# usbhub.net
KiCad netlist of a schematic drawn in Altium Designer
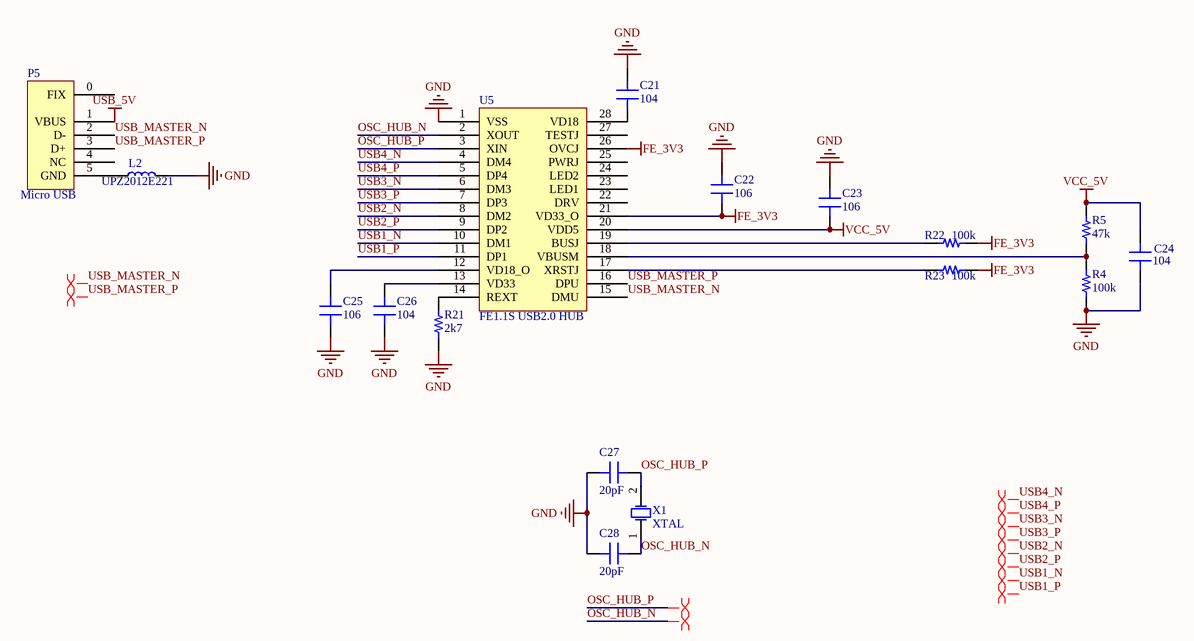
[diagram p0: usbhub.SchDoc]

(export (version "E")
  (design (tool "Eeschema 10.0.6"))
  (components
    (comp (ref "C21")
      (value "104")
      (footprint "C0603/1608")
      (description "陶瓷电容")
      (libsource (lib "Devices") (part "陶瓷电容"))
    )
    (comp (ref "C22")
      (value "106")
      (footprint "C0603/1608")
      (description "陶瓷电容")
      (libsource (lib "Devices") (part "陶瓷电容"))
    )
    (comp (ref "C23")
      (value "106")
      (footprint "C0603/1608")
      (description "陶瓷电容")
      (libsource (lib "Devices") (part "陶瓷电容"))
    )
    (comp (ref "C24")
      (value "104")
      (footprint "C0603/1608")
      (description "陶瓷电容")
      (libsource (lib "Devices") (part "陶瓷电容"))
    )
    (comp (ref "C25")
      (value "106")
      (footprint "C0603/1608")
      (description "陶瓷电容")
      (libsource (lib "Devices") (part "陶瓷电容"))
    )
    (comp (ref "C26")
      (value "104")
      (footprint "C0603/1608")
      (description "陶瓷电容")
      (libsource (lib "Devices") (part "陶瓷电容"))
    )
    (comp (ref "C27")
      (value "20pF")
      (footprint "C0603/1608")
      (description "陶瓷电容")
      (libsource (lib "Devices") (part "陶瓷电容"))
    )
    (comp (ref "C28")
      (value "20pF")
      (footprint "C0603/1608")
      (description "陶瓷电容")
      (libsource (lib "Devices") (part "陶瓷电容"))
    )
    (comp (ref "L2")
      (value "UPZ2012E221")
      (footprint "L0805/2012")
      (description "贴片磁珠")
      (libsource (lib "WMJ2019_Devices") (part "磁珠"))
    )
    (comp (ref "P5")
      (value "Micro USB")
      (footprint "Micro USB")
      (description "Micro USB底座")
      (libsource (lib "Devices") (part "Micro USB"))
    )
    (comp (ref "R4")
      (value "100k")
      (footprint "R0603/1608")
      (description "电阻")
      (libsource (lib "Devices") (part "电阻"))
    )
    (comp (ref "R5")
      (value "47k")
      (footprint "R0603/1608")
      (description "电阻")
      (libsource (lib "Devices") (part "电阻"))
    )
    (comp (ref "R21")
      (value "2k7")
      (footprint "R0603/1608")
      (description "电阻")
      (libsource (lib "Devices") (part "电阻"))
    )
    (comp (ref "R22")
      (value "100k")
      (footprint "R0603/1608")
      (description "电阻")
      (libsource (lib "Devices") (part "电阻"))
    )
    (comp (ref "R23")
      (value "100k")
      (footprint "R0603/1608")
      (description "电阻")
      (libsource (lib "Devices") (part "电阻"))
    )
    (comp (ref "U5")
      (value "FE1.1S USB2.0 HUB")
      (footprint "SOP65P780-28M")
      (libsource (lib "Devices") (part "FE1.1S USB2.0 HUB"))
    )
    (comp (ref "X1")
      (value "XTAL")
      (footprint "XTAL-49S")
      (description "晶振")
      (fields (field (name "PUBLISHER") "Altium Limited"))
      (libsource (lib "Devices") (part "晶振"))
    )
  )
  (nets
    (net (code "1") (name "/OSC_HUB_N") (class "Default")
      (node (ref "C28") (pin "1") (pintype "passive"))
      (node (ref "U5") (pin "2") (pinfunction "XOUT_2") (pintype "passive"))
      (node (ref "X1") (pin "1") (pinfunction "OSC1_1") (pintype "passive"))
    )
    (net (code "2") (name "/OSC_HUB_P") (class "Default")
      (node (ref "C27") (pin "1") (pintype "passive"))
      (node (ref "U5") (pin "3") (pinfunction "XIN_3") (pintype "passive"))
      (node (ref "X1") (pin "2") (pinfunction "OSC2_2") (pintype "passive"))
    )
    (net (code "3") (name "/USB1_N") (class "Default")
      (node (ref "U5") (pin "10") (pinfunction "DM1_10") (pintype "passive"))
    )
    (net (code "4") (name "/USB1_P") (class "Default")
      (node (ref "U5") (pin "11") (pinfunction "DP1_11") (pintype "passive"))
    )
    (net (code "5") (name "/USB2_N") (class "Default")
      (node (ref "U5") (pin "8") (pinfunction "DM2_8") (pintype "passive"))
    )
    (net (code "6") (name "/USB2_P") (class "Default")
      (node (ref "U5") (pin "9") (pinfunction "DP2_9") (pintype "passive"))
    )
    (net (code "7") (name "/USB3_N") (class "Default")
      (node (ref "U5") (pin "6") (pinfunction "DM3_6") (pintype "passive"))
    )
    (net (code "8") (name "/USB3_P") (class "Default")
      (node (ref "U5") (pin "7") (pinfunction "DP3_7") (pintype "passive"))
    )
    (net (code "9") (name "/USB4_N") (class "Default")
      (node (ref "U5") (pin "4") (pinfunction "DM4_4") (pintype "passive"))
    )
    (net (code "10") (name "/USB4_P") (class "Default")
      (node (ref "U5") (pin "5") (pinfunction "DP4_5") (pintype "passive"))
    )
    (net (code "11") (name "/USB_MASTER_N") (class "Default")
      (node (ref "P5") (pin "2") (pinfunction "D-_2") (pintype "passive"))
      (node (ref "U5") (pin "15") (pinfunction "DMU_15") (pintype "passive"))
    )
    (net (code "12") (name "/USB_MASTER_P") (class "Default")
      (node (ref "P5") (pin "3") (pinfunction "D+_3") (pintype "passive"))
      (node (ref "U5") (pin "16") (pinfunction "DPU_16") (pintype "passive"))
    )
    (net (code "13") (name "FE_3V3") (class "Default")
      (node (ref "C22") (pin "2") (pintype "passive"))
      (node (ref "R22") (pin "1") (pintype "passive"))
      (node (ref "R23") (pin "1") (pintype "passive"))
      (node (ref "U5") (pin "21") (pinfunction "VD33_O_21") (pintype "passive"))
      (node (ref "U5") (pin "26") (pinfunction "OVCJ_26") (pintype "passive"))
    )
    (net (code "14") (name "GND") (class "Default")
      (node (ref "C21") (pin "1") (pintype "passive"))
      (node (ref "C22") (pin "1") (pintype "passive"))
      (node (ref "C23") (pin "1") (pintype "passive"))
      (node (ref "C24") (pin "2") (pintype "passive"))
      (node (ref "C25") (pin "2") (pintype "passive"))
      (node (ref "C26") (pin "2") (pintype "passive"))
      (node (ref "C27") (pin "2") (pintype "passive"))
      (node (ref "C28") (pin "2") (pintype "passive"))
      (node (ref "L2") (pin "1") (pinfunction "1_1") (pintype "passive"))
      (node (ref "R21") (pin "1") (pintype "passive"))
      (node (ref "R4") (pin "2") (pintype "passive"))
      (node (ref "U5") (pin "1") (pinfunction "VSS_1") (pintype "passive"))
    )
    (net (code "15") (name "Net-(P5-GND)") (class "Default")
      (node (ref "L2") (pin "2") (pinfunction "2_2") (pintype "passive"))
      (node (ref "P5") (pin "5") (pinfunction "GND_5") (pintype "passive"))
    )
    (net (code "16") (name "Net-(U5-BUSJ)") (class "Default")
      (node (ref "R22") (pin "2") (pintype "passive"))
      (node (ref "U5") (pin "19") (pinfunction "BUSJ_19") (pintype "passive"))
    )
    (net (code "17") (name "Net-(U5-REXT)") (class "Default")
      (node (ref "R21") (pin "2") (pintype "passive"))
      (node (ref "U5") (pin "14") (pinfunction "REXT_14") (pintype "passive"))
    )
    (net (code "18") (name "Net-(U5-VBUSM)") (class "Default")
      (node (ref "R4") (pin "1") (pintype "passive"))
      (node (ref "R5") (pin "2") (pintype "passive"))
      (node (ref "U5") (pin "18") (pinfunction "VBUSM_18") (pintype "passive"))
    )
    (net (code "19") (name "Net-(U5-VD18)") (class "Default")
      (node (ref "C21") (pin "2") (pintype "passive"))
      (node (ref "U5") (pin "28") (pinfunction "VD18_28") (pintype "passive"))
    )
    (net (code "20") (name "Net-(U5-VD18_O)") (class "Default")
      (node (ref "C25") (pin "1") (pintype "passive"))
      (node (ref "U5") (pin "12") (pinfunction "VD18_O_12") (pintype "passive"))
    )
    (net (code "21") (name "Net-(U5-VD33)") (class "Default")
      (node (ref "C26") (pin "1") (pintype "passive"))
      (node (ref "U5") (pin "13") (pinfunction "VD33_13") (pintype "passive"))
    )
    (net (code "22") (name "Net-(U5-XRSTJ)") (class "Default")
      (node (ref "R23") (pin "2") (pintype "passive"))
      (node (ref "U5") (pin "17") (pinfunction "XRSTJ_17") (pintype "passive"))
    )
    (net (code "23") (name "USB_5V") (class "Default")
      (node (ref "P5") (pin "1") (pinfunction "VBUS_1") (pintype "passive"))
    )
    (net (code "24") (name "VCC_5V") (class "Default")
      (node (ref "C23") (pin "2") (pintype "passive"))
      (node (ref "C24") (pin "1") (pintype "passive"))
      (node (ref "R5") (pin "1") (pintype "passive"))
      (node (ref "U5") (pin "20") (pinfunction "VDD5_20") (pintype "passive"))
    )
    (net (code "25") (name "unconnected-(P5-FIX-Pad0)") (class "Default")
      (node (ref "P5") (pin "0") (pinfunction "FIX_0") (pintype "passive"))
    )
    (net (code "26") (name "unconnected-(P5-NC-Pad4)") (class "Default")
      (node (ref "P5") (pin "4") (pinfunction "NC_4") (pintype "passive"))
    )
    (net (code "27") (name "unconnected-(U5-DRV-Pad22)") (class "Default")
      (node (ref "U5") (pin "22") (pinfunction "DRV_22") (pintype "passive"))
    )
    (net (code "28") (name "unconnected-(U5-LED1-Pad23)") (class "Default")
      (node (ref "U5") (pin "23") (pinfunction "LED1_23") (pintype "passive"))
    )
    (net (code "29") (name "unconnected-(U5-LED2-Pad24)") (class "Default")
      (node (ref "U5") (pin "24") (pinfunction "LED2_24") (pintype "passive"))
    )
    (net (code "30") (name "unconnected-(U5-PWRJ-Pad25)") (class "Default")
      (node (ref "U5") (pin "25") (pinfunction "PWRJ_25") (pintype "passive"))
    )
    (net (code "31") (name "unconnected-(U5-TESTJ-Pad27)") (class "Default")
      (node (ref "U5") (pin "27") (pinfunction "TESTJ_27") (pintype "passive"))
    )
  )
)
